# Power.net
KiCad netlist of a schematic drawn in Altium Designer
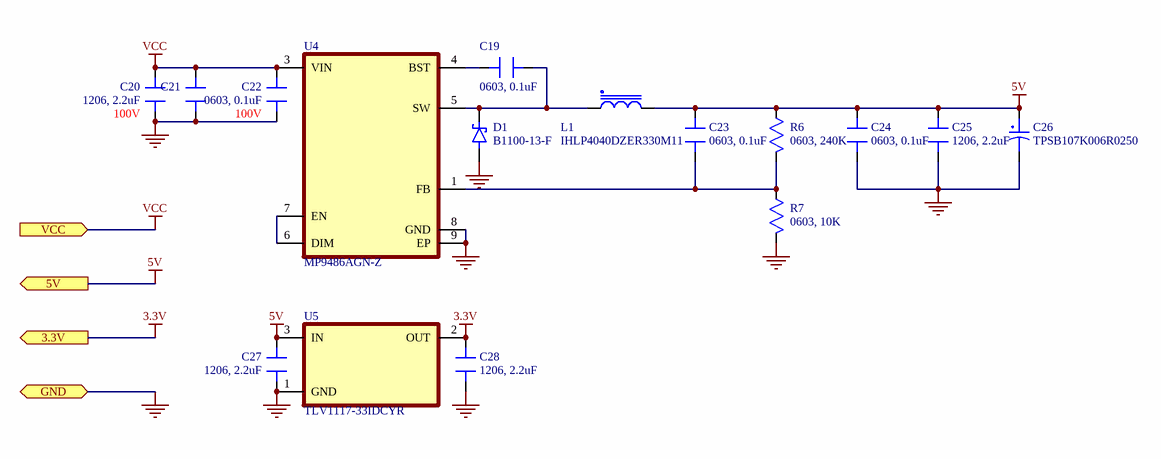
[diagram p0: Power.SchDoc]

(export (version "E")
  (design (tool "Eeschema 10.0.6"))
  (components
    (comp (ref "C19")
      (value "0603, 0.1uF")
      (footprint "CAP 0603_1608")
      (libsource (lib "Passives") (part "0603 Kapasitör"))
    )
    (comp (ref "C20")
      (value "1206, 2.2uF")
      (footprint "CAP 1206_3216")
      (fields (field (name "VOLTAGE RATING") "100V"))
      (libsource (lib "Passives") (part "1206 Kapasitör"))
    )
    (comp (ref "C21")
      (value "1206, 2.2uF")
      (footprint "CAP 1206_3216")
      (libsource (lib "Passives") (part "1206 Kapasitör"))
    )
    (comp (ref "C22")
      (value "0603, 0.1uF")
      (footprint "CAP 0603_1608")
      (fields (field (name "VOLTAGE RATING") "100V"))
      (libsource (lib "Passives") (part "0603 Kapasitör"))
    )
    (comp (ref "C23")
      (value "0603, 0.1uF")
      (footprint "CAP 0603_1608")
      (libsource (lib "Passives") (part "0603 Kapasitör"))
    )
    (comp (ref "C24")
      (value "0603, 0.1uF")
      (footprint "CAP 0603_1608")
      (libsource (lib "Passives") (part "0603 Kapasitör"))
    )
    (comp (ref "C25")
      (value "1206, 2.2uF")
      (footprint "CAP 1206_3216")
      (libsource (lib "Passives") (part "1206 Kapasitör"))
    )
    (comp (ref "C26")
      (value "TPSB107K006R0250")
      (footprint "TPSB107K006R0250")
      (libsource (lib "TPSB107K006R0250") (part "TPSB107K006R0250"))
    )
    (comp (ref "C27")
      (value "1206, 2.2uF")
      (footprint "CAP 1206_3216")
      (libsource (lib "Passives") (part "1206 Kapasitör"))
    )
    (comp (ref "C28")
      (value "1206, 2.2uF")
      (footprint "CAP 1206_3216")
      (libsource (lib "Passives") (part "1206 Kapasitör"))
    )
    (comp (ref "D1")
      (value "B1100-13-F")
      (footprint "B1100-13-F")
      (libsource (lib "B1100-13-F") (part "B1100-13-F"))
    )
    (comp (ref "L1")
      (value "IHLP4040DZER330M11")
      (footprint "IHLP4040DZER330M11")
      (libsource (lib "IHLP4040DZER330M11") (part "IHLP4040DZER330M11"))
    )
    (comp (ref "R6")
      (value "0603, 240K")
      (footprint "RES 0603_1608")
      (libsource (lib "Passives") (part "0603 Direnç"))
    )
    (comp (ref "R7")
      (value "0603, 10K")
      (footprint "RES 0603_1608")
      (libsource (lib "Passives") (part "0603 Direnç"))
    )
    (comp (ref "U4")
      (value "MP9486AGN-Z")
      (footprint "MP9486AGN-Z")
      (libsource (lib "MP9486AGN-Z") (part "MP9486AGN-Z"))
    )
    (comp (ref "U5")
      (value "TLV1117-33IDCYR")
      (footprint "TLV1117-33IDCYR")
      (libsource (lib "TLV1117-33IDCYR") (part "TLV1117-33IDCYR"))
    )
  )
  (nets
    (net (code "1") (name "3.3V") (class "Default")
      (node (ref "C28") (pin "2") (pinfunction "2_2") (pintype "passive"))
      (node (ref "U5") (pin "2") (pinfunction "OUT_2") (pintype "passive"))
    )
    (net (code "2") (name "5V") (class "Default")
      (node (ref "C23") (pin "1") (pinfunction "1_1") (pintype "passive"))
      (node (ref "C24") (pin "1") (pinfunction "1_1") (pintype "passive"))
      (node (ref "C25") (pin "2") (pinfunction "2_2") (pintype "passive"))
      (node (ref "C26") (pin "1") (pinfunction "1_1") (pintype "passive"))
      (node (ref "C27") (pin "2") (pinfunction "2_2") (pintype "passive"))
      (node (ref "L1") (pin "2") (pinfunction "2_2") (pintype "passive"))
      (node (ref "R6") (pin "2") (pinfunction "2_2") (pintype "passive"))
      (node (ref "U5") (pin "3") (pinfunction "IN_3") (pintype "passive"))
    )
    (net (code "3") (name "GND") (class "Default")
      (node (ref "C20") (pin "1") (pinfunction "1_1") (pintype "passive"))
      (node (ref "C21") (pin "1") (pinfunction "1_1") (pintype "passive"))
      (node (ref "C22") (pin "1") (pinfunction "1_1") (pintype "passive"))
      (node (ref "C24") (pin "2") (pinfunction "2_2") (pintype "passive"))
      (node (ref "C25") (pin "1") (pinfunction "1_1") (pintype "passive"))
      (node (ref "C26") (pin "2") (pinfunction "2_2") (pintype "passive"))
      (node (ref "C27") (pin "1") (pinfunction "1_1") (pintype "passive"))
      (node (ref "C28") (pin "1") (pinfunction "1_1") (pintype "passive"))
      (node (ref "D1") (pin "A") (pinfunction "A_A") (pintype "passive"))
      (node (ref "R7") (pin "1") (pinfunction "1_1") (pintype "passive"))
      (node (ref "U4") (pin "8") (pinfunction "GND_8") (pintype "passive"))
      (node (ref "U4") (pin "9") (pinfunction "EP_9") (pintype "passive"))
      (node (ref "U5") (pin "1") (pinfunction "GND_1") (pintype "passive"))
    )
    (net (code "4") (name "Net-(U4-BST)") (class "Default")
      (node (ref "C19") (pin "2") (pinfunction "2_2") (pintype "passive"))
      (node (ref "U4") (pin "4") (pinfunction "BST_4") (pintype "passive"))
    )
    (net (code "5") (name "Net-(U4-DIM)") (class "Default")
      (node (ref "U4") (pin "6") (pinfunction "DIM_6") (pintype "passive"))
      (node (ref "U4") (pin "7") (pinfunction "EN_7") (pintype "passive"))
    )
    (net (code "6") (name "Net-(U4-FB)") (class "Default")
      (node (ref "C23") (pin "2") (pinfunction "2_2") (pintype "passive"))
      (node (ref "R6") (pin "1") (pinfunction "1_1") (pintype "passive"))
      (node (ref "R7") (pin "2") (pinfunction "2_2") (pintype "passive"))
      (node (ref "U4") (pin "1") (pinfunction "FB_1") (pintype "passive"))
    )
    (net (code "7") (name "Net-(U4-SW)") (class "Default")
      (node (ref "C19") (pin "1") (pinfunction "1_1") (pintype "passive"))
      (node (ref "D1") (pin "C") (pinfunction "C_C") (pintype "passive"))
      (node (ref "L1") (pin "1") (pinfunction "1_1") (pintype "passive"))
      (node (ref "U4") (pin "5") (pinfunction "SW_5") (pintype "passive"))
    )
    (net (code "8") (name "VCC") (class "Default")
      (node (ref "C20") (pin "2") (pinfunction "2_2") (pintype "passive"))
      (node (ref "C21") (pin "2") (pinfunction "2_2") (pintype "passive"))
      (node (ref "C22") (pin "2") (pinfunction "2_2") (pintype "passive"))
      (node (ref "U4") (pin "3") (pinfunction "VIN_3") (pintype "passive"))
    )
  )
)
